# MCU_SEC.net
KiCad netlist of a schematic drawn in Altium Designer
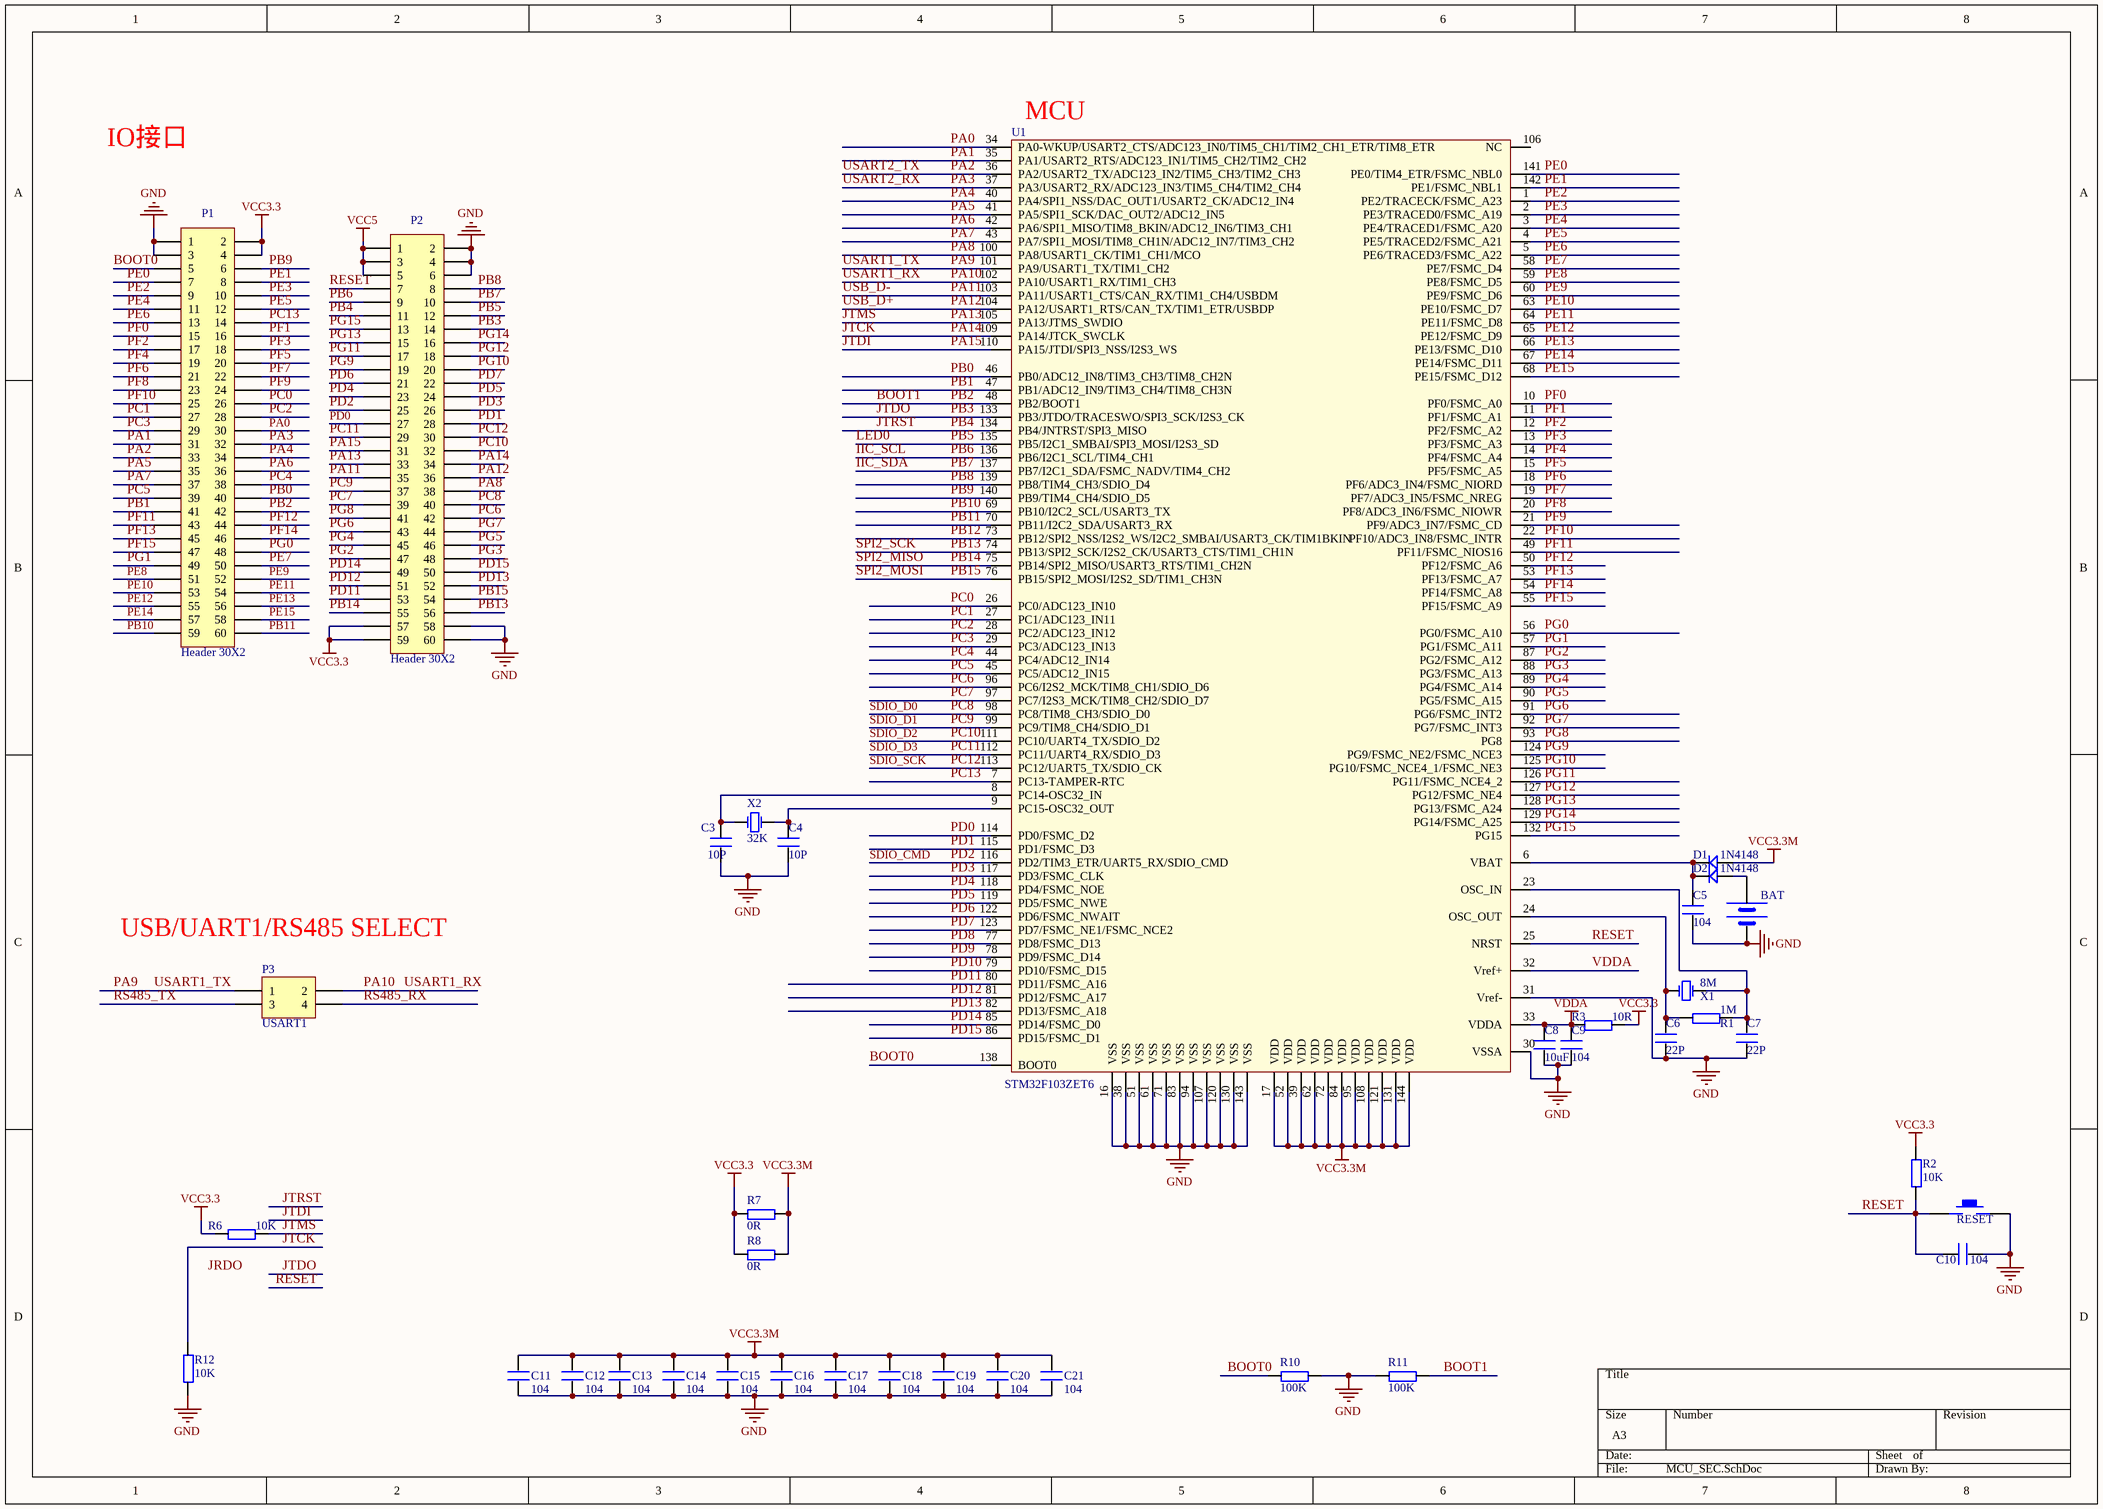
[diagram p0: MCU_SEC.SchDoc]

(export (version "E")
  (design (tool "Eeschema 10.0.6"))
  (components
    (comp (ref "BAT") (value "BATT") (footprint "BATML") (libsource (lib "战舰STM32开发板底板封装库") (part "BAT")))
    (comp (ref "C3") (value "10P") (footprint "0603CL") (libsource (lib "战舰STM32开发板底板封装库") (part "C")))
    (comp (ref "C4") (value "10P") (footprint "0603CL") (libsource (lib "战舰STM32开发板底板封装库") (part "C")))
    (comp (ref "C5") (value "104") (footprint "0603CL") (libsource (lib "战舰STM32开发板底板封装库") (part "C")))
    (comp (ref "C6") (value "22P") (footprint "0603CL") (libsource (lib "战舰STM32开发板底板封装库") (part "C")))
    (comp (ref "C7") (value "22P") (footprint "0603CL") (libsource (lib "战舰STM32开发板底板封装库") (part "C")))
    (comp (ref "C8") (value "10uF") (footprint "0603CL") (libsource (lib "战舰STM32开发板底板封装库") (part "C")))
    (comp (ref "C9") (value "104") (footprint "0603CL") (libsource (lib "战舰STM32开发板底板封装库") (part "C")))
    (comp (ref "C10") (value "104") (footprint "0603CL") (libsource (lib "战舰STM32开发板底板封装库") (part "C")))
    (comp (ref "C11") (value "104") (footprint "0603CL") (libsource (lib "战舰STM32开发板底板封装库") (part "C")))
    (comp (ref "C12") (value "104") (footprint "0603CL") (libsource (lib "战舰STM32开发板底板封装库") (part "C")))
    (comp (ref "C13") (value "104") (footprint "0603CL") (libsource (lib "战舰STM32开发板底板封装库") (part "C")))
    (comp (ref "C14") (value "104") (footprint "0603CL") (libsource (lib "战舰STM32开发板底板封装库") (part "C")))
    (comp (ref "C15") (value "104") (footprint "0603CL") (libsource (lib "战舰STM32开发板底板封装库") (part "C")))
    (comp (ref "C16") (value "104") (footprint "0603CL") (libsource (lib "战舰STM32开发板底板封装库") (part "C")))
    (comp (ref "C17") (value "104") (footprint "0603CL") (libsource (lib "战舰STM32开发板底板封装库") (part "C")))
    (comp (ref "C18") (value "104") (footprint "0603CL") (libsource (lib "战舰STM32开发板底板封装库") (part "C")))
    (comp (ref "C19") (value "104") (footprint "0603CL") (libsource (lib "战舰STM32开发板底板封装库") (part "C")))
    (comp (ref "C20") (value "104") (footprint "0603CL") (libsource (lib "战舰STM32开发板底板封装库") (part "C")))
    (comp (ref "C21") (value "104") (footprint "0603CL") (libsource (lib "战舰STM32开发板底板封装库") (part "C")))
    (comp (ref "D1")
      (value "1N4148")
      (footprint "LL-34(1/2)L")
      (libsource (lib "战舰STM32开发板底板封装库") (part "D"))
    )
    (comp (ref "D2")
      (value "1N4148")
      (footprint "LL-34(1/2)L")
      (libsource (lib "战舰STM32开发板底板封装库") (part "D"))
    )
    (comp (ref "P1")
      (value "Header 30X2")
      (footprint "HDR2X30")
      (description "Header, 30-Pin, Dual row")
      (fields (field (name "PUBLISHER") "Altium Limited"))
      (libsource (lib "Miscellaneous Connectors") (part "Header 30X2"))
    )
    (comp (ref "P2")
      (value "Header 30X2")
      (footprint "HDR2X30")
      (description "Header, 30-Pin, Dual row")
      (fields (field (name "PUBLISHER") "Altium Limited"))
      (libsource (lib "Miscellaneous Connectors") (part "Header 30X2"))
    )
    (comp (ref "P3")
      (value "USART1")
      (footprint "HDR2X2")
      (description "Header, 2-Pin, Dual row")
      (fields (field (name "PUBLISHER") "Altium Limited"))
      (libsource (lib "Miscellaneous Connectors") (part "Header 2X2"))
    )
    (comp (ref "R1") (value "1M") (footprint "0603L") (libsource (lib "战舰STM32开发板底板封装库") (part "R")))
    (comp (ref "R2") (value "10K") (footprint "0603L") (libsource (lib "战舰STM32开发板底板封装库") (part "R")))
    (comp (ref "R3") (value "10R") (footprint "0603L") (libsource (lib "战舰STM32开发板底板封装库") (part "R")))
    (comp (ref "R6") (value "10K") (footprint "0603L") (libsource (lib "战舰STM32开发板底板封装库") (part "R")))
    (comp (ref "R7") (value "0R") (footprint "0603L") (libsource (lib "战舰STM32开发板底板封装库") (part "R")))
    (comp (ref "R8") (value "0R") (footprint "0603L") (libsource (lib "战舰STM32开发板底板封装库") (part "R")))
    (comp (ref "R10") (value "100K") (footprint "0603L") (libsource (lib "战舰STM32开发板底板封装库") (part "R")))
    (comp (ref "R11") (value "100K") (footprint "0603L") (libsource (lib "战舰STM32开发板底板封装库") (part "R")))
    (comp (ref "R12") (value "10K") (footprint "0603L") (libsource (lib "战舰STM32开发板底板封装库") (part "R")))
    (comp (ref "RESET")
      (value "KEY_M")
      (footprint "SW2 - MINI1")
      (libsource (lib "战舰STM32开发板底板封装库") (part "KEY_M"))
    )
    (comp (ref "U1")
      (value "STM32F103ZET6")
      (footprint "LQFP144L")
      (libsource (lib "战舰STM32开发板底板封装库") (part "STM32F103ZET6"))
    )
    (comp (ref "X1")
      (value "8M")
      (footprint "OSC-5032-2P")
      (description "Crystal Oscillator")
      (fields (field (name "PUBLISHER") "Altium Limited"))
      (libsource (lib "常用元件库") (part "XTAL_1"))
    )
    (comp (ref "X2")
      (value "32K")
      (footprint "OSC-306")
      (description "Crystal Oscillator")
      (fields (field (name "PUBLISHER") "Altium Limited"))
      (libsource (lib "常用元件库") (part "XTAL_1"))
    )
  )
  (nets
    (net (code "1") (name "/BOOT0") (class "Default")
      (node (ref "P1") (pin "5") (pinfunction "5_5") (pintype "passive"))
      (node (ref "R10") (pin "1") (pintype "passive"))
      (node (ref "U1") (pin "138") (pinfunction "BOOT0_138") (pintype "passive"))
    )
    (net (code "2") (name "/BOOT1") (class "Default")
      (node (ref "P1") (pin "42") (pinfunction "42_42") (pintype "passive"))
      (node (ref "R11") (pin "2") (pintype "passive"))
      (node (ref "U1") (pin "48") (pinfunction "PB2/BOOT1_48") (pintype "passive"))
    )
    (net (code "3") (name "/IIC_SCL") (class "Default")
      (node (ref "P2") (pin "9") (pinfunction "9_9") (pintype "passive"))
      (node (ref "U1") (pin "136") (pinfunction "PB6/I2C1_SCL/TIM4_CH1_136") (pintype "passive"))
    )
    (net (code "4") (name "/IIC_SDA") (class "Default")
      (node (ref "P2") (pin "10") (pinfunction "10_10") (pintype "passive"))
      (node (ref "U1") (pin "137") (pinfunction "PB7/I2C1_SDA/FSMC_NADV/TIM4_CH2_137") (pintype "passive"))
    )
    (net (code "6") (name "/JTCK") (class "Default")
      (node (ref "P2") (pin "34") (pinfunction "34_34") (pintype "passive"))
      (node (ref "R12") (pin "2") (pintype "passive"))
      (node (ref "U1") (pin "109") (pinfunction "PA14/JTCK_SWCLK_109") (pintype "passive"))
    )
    (net (code "7") (name "/JTDI") (class "Default")
      (node (ref "P2") (pin "31") (pinfunction "31_31") (pintype "passive"))
      (node (ref "U1") (pin "110") (pinfunction "PA15/JTDI/SPI3_NSS/I2S3_WS_110") (pintype "passive"))
    )
    (net (code "8") (name "/JTDO") (class "Default")
      (node (ref "P2") (pin "14") (pinfunction "14_14") (pintype "passive"))
      (node (ref "U1") (pin "133") (pinfunction "PB3/JTDO/TRACESWO/SPI3_SCK/I2S3_CK_133") (pintype "passive"))
    )
    (net (code "9") (name "/JTMS") (class "Default")
      (node (ref "P2") (pin "33") (pinfunction "33_33") (pintype "passive"))
      (node (ref "R6") (pin "2") (pintype "passive"))
      (node (ref "U1") (pin "105") (pinfunction "PA13/JTMS_SWDIO_105") (pintype "passive"))
    )
    (net (code "10") (name "/JTRST") (class "Default")
      (node (ref "P2") (pin "11") (pinfunction "11_11") (pintype "passive"))
      (node (ref "U1") (pin "134") (pinfunction "PB4/JNTRST/SPI3_MISO_134") (pintype "passive"))
    )
    (net (code "11") (name "/LED0") (class "Default")
      (node (ref "P2") (pin "12") (pinfunction "12_12") (pintype "passive"))
      (node (ref "U1") (pin "135") (pinfunction "PB5/I2C1_SMBAI/SPI3_MOSI/I2S3_SD_135") (pintype "passive"))
    )
    (net (code "12") (name "/PA0") (class "Default")
      (node (ref "P1") (pin "30") (pinfunction "30_30") (pintype "passive"))
      (node (ref "U1") (pin "34") (pinfunction "PA0-WKUP/USART2_CTS/ADC123_IN0/TIM5_CH1/TIM2_CH1_ETR/TIM8_ETR_34") (pintype "passive"))
    )
    (net (code "13") (name "/PA1") (class "Default")
      (node (ref "P1") (pin "31") (pinfunction "31_31") (pintype "passive"))
      (node (ref "U1") (pin "35") (pinfunction "PA1/USART2_RTS/ADC123_IN1/TIM5_CH2/TIM2_CH2_35") (pintype "passive"))
    )
    (net (code "14") (name "/PA2") (class "Default")
      (node (ref "P1") (pin "33") (pinfunction "33_33") (pintype "passive"))
      (node (ref "U1") (pin "36") (pinfunction "PA2/USART2_TX/ADC123_IN2/TIM5_CH3/TIM2_CH3_36") (pintype "passive"))
    )
    (net (code "15") (name "/PA3") (class "Default")
      (node (ref "P1") (pin "32") (pinfunction "32_32") (pintype "passive"))
      (node (ref "U1") (pin "37") (pinfunction "PA3/USART2_RX/ADC123_IN3/TIM5_CH4/TIM2_CH4_37") (pintype "passive"))
    )
    (net (code "16") (name "/PA4") (class "Default")
      (node (ref "P1") (pin "34") (pinfunction "34_34") (pintype "passive"))
      (node (ref "U1") (pin "40") (pinfunction "PA4/SPI1_NSS/DAC_OUT1/USART2_CK/ADC12_IN4_40") (pintype "passive"))
    )
    (net (code "17") (name "/PA5") (class "Default")
      (node (ref "P1") (pin "35") (pinfunction "35_35") (pintype "passive"))
      (node (ref "U1") (pin "41") (pinfunction "PA5/SPI1_SCK/DAC_OUT2/ADC12_IN5_41") (pintype "passive"))
    )
    (net (code "18") (name "/PA6") (class "Default")
      (node (ref "P1") (pin "36") (pinfunction "36_36") (pintype "passive"))
      (node (ref "U1") (pin "42") (pinfunction "PA6/SPI1_MISO/TIM8_BKIN/ADC12_IN6/TIM3_CH1_42") (pintype "passive"))
    )
    (net (code "19") (name "/PA7") (class "Default")
      (node (ref "P1") (pin "37") (pinfunction "37_37") (pintype "passive"))
      (node (ref "U1") (pin "43") (pinfunction "PA7/SPI1_MOSI/TIM8_CH1N/ADC12_IN7/TIM3_CH2_43") (pintype "passive"))
    )
    (net (code "20") (name "/PA8") (class "Default")
      (node (ref "P2") (pin "38") (pinfunction "38_38") (pintype "passive"))
      (node (ref "U1") (pin "100") (pinfunction "PA8/USART1_CK/TIM1_CH1/MCO_100") (pintype "passive"))
    )
    (net (code "21") (name "/PA9") (class "Default")
      (node (ref "P3") (pin "1") (pinfunction "1_1") (pintype "passive"))
      (node (ref "U1") (pin "101") (pinfunction "PA9/USART1_TX/TIM1_CH2_101") (pintype "passive"))
    )
    (net (code "22") (name "/PA10") (class "Default")
      (node (ref "P3") (pin "2") (pinfunction "2_2") (pintype "passive"))
      (node (ref "U1") (pin "102") (pinfunction "PA10/USART1_RX/TIM1_CH3_102") (pintype "passive"))
    )
    (net (code "23") (name "/PA11") (class "Default")
      (node (ref "P2") (pin "35") (pinfunction "35_35") (pintype "passive"))
      (node (ref "U1") (pin "103") (pinfunction "PA11/USART1_CTS/CAN_RX/TIM1_CH4/USBDM_103") (pintype "passive"))
    )
    (net (code "24") (name "/PA12") (class "Default")
      (node (ref "P2") (pin "36") (pinfunction "36_36") (pintype "passive"))
      (node (ref "U1") (pin "104") (pinfunction "PA12/USART1_RTS/CAN_TX/TIM1_ETR/USBDP_104") (pintype "passive"))
    )
    (net (code "25") (name "/PB0") (class "Default")
      (node (ref "P1") (pin "40") (pinfunction "40_40") (pintype "passive"))
      (node (ref "U1") (pin "46") (pinfunction "PB0/ADC12_IN8/TIM3_CH3/TIM8_CH2N_46") (pintype "passive"))
    )
    (net (code "26") (name "/PB1") (class "Default")
      (node (ref "P1") (pin "41") (pinfunction "41_41") (pintype "passive"))
      (node (ref "U1") (pin "47") (pinfunction "PB1/ADC12_IN9/TIM3_CH4/TIM8_CH3N_47") (pintype "passive"))
    )
    (net (code "27") (name "/PB8") (class "Default")
      (node (ref "P2") (pin "8") (pinfunction "8_8") (pintype "passive"))
      (node (ref "U1") (pin "139") (pinfunction "PB8/TIM4_CH3/SDIO_D4_139") (pintype "passive"))
    )
    (net (code "28") (name "/PB9") (class "Default")
      (node (ref "P1") (pin "6") (pinfunction "6_6") (pintype "passive"))
      (node (ref "U1") (pin "140") (pinfunction "PB9/TIM4_CH4/SDIO_D5_140") (pintype "passive"))
    )
    (net (code "29") (name "/PB10") (class "Default")
      (node (ref "P1") (pin "59") (pinfunction "59_59") (pintype "passive"))
      (node (ref "U1") (pin "69") (pinfunction "PB10/I2C2_SCL/USART3_TX_69") (pintype "passive"))
    )
    (net (code "30") (name "/PB11") (class "Default")
      (node (ref "P1") (pin "60") (pinfunction "60_60") (pintype "passive"))
      (node (ref "U1") (pin "70") (pinfunction "PB11/I2C2_SDA/USART3_RX_70") (pintype "passive"))
    )
    (net (code "31") (name "/PB12") (class "Default")
      (node (ref "U1") (pin "73") (pinfunction "PB12/SPI2_NSS/I2S2_WS/I2C2_SMBAI/USART3_CK/TIM1BKIN_73") (pintype "passive"))
    )
    (net (code "32") (name "/PB13") (class "Default")
      (node (ref "P2") (pin "56") (pinfunction "56_56") (pintype "passive"))
      (node (ref "U1") (pin "74") (pinfunction "PB13/SPI2_SCK/I2S2_CK/USART3_CTS/TIM1_CH1N_74") (pintype "passive"))
    )
    (net (code "33") (name "/PB14") (class "Default")
      (node (ref "P2") (pin "55") (pinfunction "55_55") (pintype "passive"))
      (node (ref "U1") (pin "75") (pinfunction "PB14/SPI2_MISO/USART3_RTS/TIM1_CH2N_75") (pintype "passive"))
    )
    (net (code "34") (name "/PB15") (class "Default")
      (node (ref "P2") (pin "54") (pinfunction "54_54") (pintype "passive"))
      (node (ref "U1") (pin "76") (pinfunction "PB15/SPI2_MOSI/I2S2_SD/TIM1_CH3N_76") (pintype "passive"))
    )
    (net (code "35") (name "/PC0") (class "Default")
      (node (ref "P1") (pin "26") (pinfunction "26_26") (pintype "passive"))
      (node (ref "U1") (pin "26") (pinfunction "PC0/ADC123_IN10_26") (pintype "passive"))
    )
    (net (code "36") (name "/PC1") (class "Default")
      (node (ref "P1") (pin "27") (pinfunction "27_27") (pintype "passive"))
      (node (ref "U1") (pin "27") (pinfunction "PC1/ADC123_IN11_27") (pintype "passive"))
    )
    (net (code "37") (name "/PC2") (class "Default")
      (node (ref "P1") (pin "28") (pinfunction "28_28") (pintype "passive"))
      (node (ref "U1") (pin "28") (pinfunction "PC2/ADC123_IN12_28") (pintype "passive"))
    )
    (net (code "38") (name "/PC3") (class "Default")
      (node (ref "P1") (pin "29") (pinfunction "29_29") (pintype "passive"))
      (node (ref "U1") (pin "29") (pinfunction "PC3/ADC123_IN13_29") (pintype "passive"))
    )
    (net (code "39") (name "/PC4") (class "Default")
      (node (ref "P1") (pin "38") (pinfunction "38_38") (pintype "passive"))
      (node (ref "U1") (pin "44") (pinfunction "PC4/ADC12_IN14_44") (pintype "passive"))
    )
    (net (code "40") (name "/PC5") (class "Default")
      (node (ref "P1") (pin "39") (pinfunction "39_39") (pintype "passive"))
      (node (ref "U1") (pin "45") (pinfunction "PC5/ADC12_IN15_45") (pintype "passive"))
    )
    (net (code "41") (name "/PC6") (class "Default")
      (node (ref "P2") (pin "42") (pinfunction "42_42") (pintype "passive"))
      (node (ref "U1") (pin "96") (pinfunction "PC6/I2S2_MCK/TIM8_CH1/SDIO_D6_96") (pintype "passive"))
    )
    (net (code "42") (name "/PC7") (class "Default")
      (node (ref "P2") (pin "39") (pinfunction "39_39") (pintype "passive"))
      (node (ref "U1") (pin "97") (pinfunction "PC7/I2S3_MCK/TIM8_CH2/SDIO_D7_97") (pintype "passive"))
    )
    (net (code "43") (name "/PC8") (class "Default")
      (node (ref "P2") (pin "40") (pinfunction "40_40") (pintype "passive"))
      (node (ref "U1") (pin "98") (pinfunction "PC8/TIM8_CH3/SDIO_D0_98") (pintype "passive"))
    )
    (net (code "44") (name "/PC9") (class "Default")
      (node (ref "P2") (pin "37") (pinfunction "37_37") (pintype "passive"))
      (node (ref "U1") (pin "99") (pinfunction "PC9/TIM8_CH4/SDIO_D1_99") (pintype "passive"))
    )
    (net (code "45") (name "/PC10") (class "Default")
      (node (ref "P2") (pin "32") (pinfunction "32_32") (pintype "passive"))
      (node (ref "U1") (pin "111") (pinfunction "PC10/UART4_TX/SDIO_D2_111") (pintype "passive"))
    )
    (net (code "46") (name "/PC11") (class "Default")
      (node (ref "P2") (pin "29") (pinfunction "29_29") (pintype "passive"))
      (node (ref "U1") (pin "112") (pinfunction "PC11/UART4_RX/SDIO_D3_112") (pintype "passive"))
    )
    (net (code "47") (name "/PC12") (class "Default")
      (node (ref "P2") (pin "30") (pinfunction "30_30") (pintype "passive"))
      (node (ref "U1") (pin "113") (pinfunction "PC12/UART5_TX/SDIO_CK_113") (pintype "passive"))
    )
    (net (code "48") (name "/PC13") (class "Default")
      (node (ref "P1") (pin "14") (pinfunction "14_14") (pintype "passive"))
      (node (ref "U1") (pin "7") (pinfunction "PC13-TAMPER-RTC_7") (pintype "passive"))
    )
    (net (code "49") (name "/PD0") (class "Default")
      (node (ref "P2") (pin "27") (pinfunction "27_27") (pintype "passive"))
      (node (ref "U1") (pin "114") (pinfunction "PD0/FSMC_D2_114") (pintype "passive"))
    )
    (net (code "50") (name "/PD1") (class "Default")
      (node (ref "P2") (pin "28") (pinfunction "28_28") (pintype "passive"))
      (node (ref "U1") (pin "115") (pinfunction "PD1/FSMC_D3_115") (pintype "passive"))
    )
    (net (code "51") (name "/PD2") (class "Default")
      (node (ref "P2") (pin "25") (pinfunction "25_25") (pintype "passive"))
      (node (ref "U1") (pin "116") (pinfunction "PD2/TIM3_ETR/UART5_RX/SDIO_CMD_116") (pintype "passive"))
    )
    (net (code "52") (name "/PD3") (class "Default")
      (node (ref "P2") (pin "26") (pinfunction "26_26") (pintype "passive"))
      (node (ref "U1") (pin "117") (pinfunction "PD3/FSMC_CLK_117") (pintype "passive"))
    )
    (net (code "53") (name "/PD4") (class "Default")
      (node (ref "P2") (pin "23") (pinfunction "23_23") (pintype "passive"))
      (node (ref "U1") (pin "118") (pinfunction "PD4/FSMC_NOE_118") (pintype "passive"))
    )
    (net (code "54") (name "/PD5") (class "Default")
      (node (ref "P2") (pin "24") (pinfunction "24_24") (pintype "passive"))
      (node (ref "U1") (pin "119") (pinfunction "PD5/FSMC_NWE_119") (pintype "passive"))
    )
    (net (code "55") (name "/PD6") (class "Default")
      (node (ref "P2") (pin "21") (pinfunction "21_21") (pintype "passive"))
      (node (ref "U1") (pin "122") (pinfunction "PD6/FSMC_NWAIT_122") (pintype "passive"))
    )
    (net (code "56") (name "/PD7") (class "Default")
      (node (ref "P2") (pin "22") (pinfunction "22_22") (pintype "passive"))
      (node (ref "U1") (pin "123") (pinfunction "PD7/FSMC_NE1/FSMC_NCE2_123") (pintype "passive"))
    )
    (net (code "57") (name "/PD8") (class "Default")
      (node (ref "U1") (pin "77") (pinfunction "PD8/FSMC_D13_77") (pintype "passive"))
    )
    (net (code "58") (name "/PD9") (class "Default")
      (node (ref "U1") (pin "78") (pinfunction "PD9/FSMC_D14_78") (pintype "passive"))
    )
    (net (code "59") (name "/PD10") (class "Default")
      (node (ref "U1") (pin "79") (pinfunction "PD10/FSMC_D15_79") (pintype "passive"))
    )
    (net (code "60") (name "/PD11") (class "Default")
      (node (ref "P2") (pin "53") (pinfunction "53_53") (pintype "passive"))
      (node (ref "U1") (pin "80") (pinfunction "PD11/FSMC_A16_80") (pintype "passive"))
    )
    (net (code "61") (name "/PD12") (class "Default")
      (node (ref "P2") (pin "51") (pinfunction "51_51") (pintype "passive"))
      (node (ref "U1") (pin "81") (pinfunction "PD12/FSMC_A17_81") (pintype "passive"))
    )
    (net (code "62") (name "/PD13") (class "Default")
      (node (ref "P2") (pin "52") (pinfunction "52_52") (pintype "passive"))
      (node (ref "U1") (pin "82") (pinfunction "PD13/FSMC_A18_82") (pintype "passive"))
    )
    (net (code "63") (name "/PD14") (class "Default")
      (node (ref "P2") (pin "49") (pinfunction "49_49") (pintype "passive"))
      (node (ref "U1") (pin "85") (pinfunction "PD14/FSMC_D0_85") (pintype "passive"))
    )
    (net (code "64") (name "/PD15") (class "Default")
      (node (ref "P2") (pin "50") (pinfunction "50_50") (pintype "passive"))
      (node (ref "U1") (pin "86") (pinfunction "PD15/FSMC_D1_86") (pintype "passive"))
    )
    (net (code "65") (name "/PE0") (class "Default")
      (node (ref "P1") (pin "7") (pinfunction "7_7") (pintype "passive"))
      (node (ref "U1") (pin "141") (pinfunction "PE0/TIM4_ETR/FSMC_NBL0_141") (pintype "passive"))
    )
    (net (code "66") (name "/PE1") (class "Default")
      (node (ref "P1") (pin "8") (pinfunction "8_8") (pintype "passive"))
      (node (ref "U1") (pin "142") (pinfunction "PE1/FSMC_NBL1_142") (pintype "passive"))
    )
    (net (code "67") (name "/PE2") (class "Default")
      (node (ref "P1") (pin "9") (pinfunction "9_9") (pintype "passive"))
      (node (ref "U1") (pin "1") (pinfunction "PE2/TRACECK/FSMC_A23_1") (pintype "passive"))
    )
    (net (code "68") (name "/PE3") (class "Default")
      (node (ref "P1") (pin "10") (pinfunction "10_10") (pintype "passive"))
      (node (ref "U1") (pin "2") (pinfunction "PE3/TRACED0/FSMC_A19_2") (pintype "passive"))
    )
    (net (code "69") (name "/PE4") (class "Default")
      (node (ref "P1") (pin "11") (pinfunction "11_11") (pintype "passive"))
      (node (ref "U1") (pin "3") (pinfunction "PE4/TRACED1/FSMC_A20_3") (pintype "passive"))
    )
    (net (code "70") (name "/PE5") (class "Default")
      (node (ref "P1") (pin "12") (pinfunction "12_12") (pintype "passive"))
      (node (ref "U1") (pin "4") (pinfunction "PE5/TRACED2/FSMC_A21_4") (pintype "passive"))
    )
    (net (code "71") (name "/PE6") (class "Default")
      (node (ref "P1") (pin "13") (pinfunction "13_13") (pintype "passive"))
      (node (ref "U1") (pin "5") (pinfunction "PE6/TRACED3/FSMC_A22_5") (pintype "passive"))
    )
    (net (code "72") (name "/PE7") (class "Default")
      (node (ref "P1") (pin "50") (pinfunction "50_50") (pintype "passive"))
      (node (ref "U1") (pin "58") (pinfunction "PE7/FSMC_D4_58") (pintype "passive"))
    )
    (net (code "73") (name "/PE8") (class "Default")
      (node (ref "P1") (pin "51") (pinfunction "51_51") (pintype "passive"))
      (node (ref "U1") (pin "59") (pinfunction "PE8/FSMC_D5_59") (pintype "passive"))
    )
    (net (code "74") (name "/PE9") (class "Default")
      (node (ref "P1") (pin "52") (pinfunction "52_52") (pintype "passive"))
      (node (ref "U1") (pin "60") (pinfunction "PE9/FSMC_D6_60") (pintype "passive"))
    )
    (net (code "75") (name "/PE10") (class "Default")
      (node (ref "P1") (pin "53") (pinfunction "53_53") (pintype "passive"))
      (node (ref "U1") (pin "63") (pinfunction "PE10/FSMC_D7_63") (pintype "passive"))
    )
    (net (code "76") (name "/PE11") (class "Default")
      (node (ref "P1") (pin "54") (pinfunction "54_54") (pintype "passive"))
      (node (ref "U1") (pin "64") (pinfunction "PE11/FSMC_D8_64") (pintype "passive"))
    )
    (net (code "77") (name "/PE12") (class "Default")
      (node (ref "P1") (pin "55") (pinfunction "55_55") (pintype "passive"))
      (node (ref "U1") (pin "65") (pinfunction "PE12/FSMC_D9_65") (pintype "passive"))
    )
    (net (code "78") (name "/PE13") (class "Default")
      (node (ref "P1") (pin "56") (pinfunction "56_56") (pintype "passive"))
      (node (ref "U1") (pin "66") (pinfunction "PE13/FSMC_D10_66") (pintype "passive"))
    )
    (net (code "79") (name "/PE14") (class "Default")
      (node (ref "P1") (pin "57") (pinfunction "57_57") (pintype "passive"))
      (node (ref "U1") (pin "67") (pinfunction "PE14/FSMC_D11_67") (pintype "passive"))
    )
    (net (code "80") (name "/PE15") (class "Default")
      (node (ref "P1") (pin "58") (pinfunction "58_58") (pintype "passive"))
      (node (ref "U1") (pin "68") (pinfunction "PE15/FSMC_D12_68") (pintype "passive"))
    )
    (net (code "81") (name "/PF0") (class "Default")
      (node (ref "P1") (pin "15") (pinfunction "15_15") (pintype "passive"))
      (node (ref "U1") (pin "10") (pinfunction "PF0/FSMC_A0_10") (pintype "passive"))
    )
    (net (code "82") (name "/PF1") (class "Default")
      (node (ref "P1") (pin "16") (pinfunction "16_16") (pintype "passive"))
      (node (ref "U1") (pin "11") (pinfunction "PF1/FSMC_A1_11") (pintype "passive"))
    )
    (net (code "83") (name "/PF2") (class "Default")
      (node (ref "P1") (pin "17") (pinfunction "17_17") (pintype "passive"))
      (node (ref "U1") (pin "12") (pinfunction "PF2/FSMC_A2_12") (pintype "passive"))
    )
    (net (code "84") (name "/PF3") (class "Default")
      (node (ref "P1") (pin "18") (pinfunction "18_18") (pintype "passive"))
      (node (ref "U1") (pin "13") (pinfunction "PF3/FSMC_A3_13") (pintype "passive"))
    )
    (net (code "85") (name "/PF4") (class "Default")
      (node (ref "P1") (pin "19") (pinfunction "19_19") (pintype "passive"))
      (node (ref "U1") (pin "14") (pinfunction "PF4/FSMC_A4_14") (pintype "passive"))
    )
    (net (code "86") (name "/PF5") (class "Default")
      (node (ref "P1") (pin "20") (pinfunction "20_20") (pintype "passive"))
      (node (ref "U1") (pin "15") (pinfunction "PF5/FSMC_A5_15") (pintype "passive"))
    )
    (net (code "87") (name "/PF6") (class "Default")
      (node (ref "P1") (pin "21") (pinfunction "21_21") (pintype "passive"))
      (node (ref "U1") (pin "18") (pinfunction "PF6/ADC3_IN4/FSMC_NIORD_18") (pintype "passive"))
    )
    (net (code "88") (name "/PF7") (class "Default")
      (node (ref "P1") (pin "22") (pinfunction "22_22") (pintype "passive"))
      (node (ref "U1") (pin "19") (pinfunction "PF7/ADC3_IN5/FSMC_NREG_19") (pintype "passive"))
    )
    (net (code "89") (name "/PF8") (class "Default")
      (node (ref "P1") (pin "23") (pinfunction "23_23") (pintype "passive"))
      (node (ref "U1") (pin "20") (pinfunction "PF8/ADC3_IN6/FSMC_NIOWR_20") (pintype "passive"))
    )
    (net (code "90") (name "/PF9") (class "Default")
      (node (ref "P1") (pin "24") (pinfunction "24_24") (pintype "passive"))
      (node (ref "U1") (pin "21") (pinfunction "PF9/ADC3_IN7/FSMC_CD_21") (pintype "passive"))
    )
    (net (code "91") (name "/PF10") (class "Default")
      (node (ref "P1") (pin "25") (pinfunction "25_25") (pintype "passive"))
      (node (ref "U1") (pin "22") (pinfunction "PF10/ADC3_IN8/FSMC_INTR_22") (pintype "passive"))
    )
    (net (code "92") (name "/PF11") (class "Default")
      (node (ref "P1") (pin "43") (pinfunction "43_43") (pintype "passive"))
      (node (ref "U1") (pin "49") (pinfunction "PF11/FSMC_NIOS16_49") (pintype "passive"))
    )
    (net (code "93") (name "/PF12") (class "Default")
      (node (ref "P1") (pin "44") (pinfunction "44_44") (pintype "passive"))
      (node (ref "U1") (pin "50") (pinfunction "PF12/FSMC_A6_50") (pintype "passive"))
    )
    (net (code "94") (name "/PF13") (class "Default")
      (node (ref "P1") (pin "45") (pinfunction "45_45") (pintype "passive"))
      (node (ref "U1") (pin "53") (pinfunction "PF13/FSMC_A7_53") (pintype "passive"))
    )
    (net (code "95") (name "/PF14") (class "Default")
      (node (ref "P1") (pin "46") (pinfunction "46_46") (pintype "passive"))
      (node (ref "U1") (pin "54") (pinfunction "PF14/FSMC_A8_54") (pintype "passive"))
    )
    (net (code "96") (name "/PF15") (class "Default")
      (node (ref "P1") (pin "47") (pinfunction "47_47") (pintype "passive"))
      (node (ref "U1") (pin "55") (pinfunction "PF15/FSMC_A9_55") (pintype "passive"))
    )
    (net (code "97") (name "/PG0") (class "Default")
      (node (ref "P1") (pin "48") (pinfunction "48_48") (pintype "passive"))
      (node (ref "U1") (pin "56") (pinfunction "PG0/FSMC_A10_56") (pintype "passive"))
    )
    (net (code "98") (name "/PG1") (class "Default")
      (node (ref "P1") (pin "49") (pinfunction "49_49") (pintype "passive"))
      (node (ref "U1") (pin "57") (pinfunction "PG1/FSMC_A11_57") (pintype "passive"))
    )
    (net (code "99") (name "/PG2") (class "Default")
      (node (ref "P2") (pin "47") (pinfunction "47_47") (pintype "passive"))
      (node (ref "U1") (pin "87") (pinfunction "PG2/FSMC_A12_87") (pintype "passive"))
    )
    (net (code "100") (name "/PG3") (class "Default")
      (node (ref "P2") (pin "48") (pinfunction "48_48") (pintype "passive"))
      (node (ref "U1") (pin "88") (pinfunction "PG3/FSMC_A13_88") (pintype "passive"))
    )
    (net (code "101") (name "/PG4") (class "Default")
      (node (ref "P2") (pin "45") (pinfunction "45_45") (pintype "passive"))
      (node (ref "U1") (pin "89") (pinfunction "PG4/FSMC_A14_89") (pintype "passive"))
    )
    (net (code "102") (name "/PG5") (class "Default")
      (node (ref "P2") (pin "46") (pinfunction "46_46") (pintype "passive"))
      (node (ref "U1") (pin "90") (pinfunction "PG5/FSMC_A15_90") (pintype "passive"))
    )
    (net (code "103") (name "/PG6") (class "Default")
      (node (ref "P2") (pin "43") (pinfunction "43_43") (pintype "passive"))
      (node (ref "U1") (pin "91") (pinfunction "PG6/FSMC_INT2_91") (pintype "passive"))
    )
    (net (code "104") (name "/PG7") (class "Default")
      (node (ref "P2") (pin "44") (pinfunction "44_44") (pintype "passive"))
      (node (ref "U1") (pin "92") (pinfunction "PG7/FSMC_INT3_92") (pintype "passive"))
    )
    (net (code "105") (name "/PG8") (class "Default")
      (node (ref "P2") (pin "41") (pinfunction "41_41") (pintype "passive"))
      (node (ref "U1") (pin "93") (pinfunction "PG8_93") (pintype "passive"))
    )
    (net (code "106") (name "/PG9") (class "Default")
      (node (ref "P2") (pin "19") (pinfunction "19_19") (pintype "passive"))
      (node (ref "U1") (pin "124") (pinfunction "PG9/FSMC_NE2/FSMC_NCE3_124") (pintype "passive"))
    )
    (net (code "107") (name "/PG10") (class "Default")
      (node (ref "P2") (pin "20") (pinfunction "20_20") (pintype "passive"))
      (node (ref "U1") (pin "125") (pinfunction "PG10/FSMC_NCE4_1/FSMC_NE3_125") (pintype "passive"))
    )
    (net (code "108") (name "/PG11") (class "Default")
      (node (ref "P2") (pin "17") (pinfunction "17_17") (pintype "passive"))
      (node (ref "U1") (pin "126") (pinfunction "PG11/FSMC_NCE4_2_126") (pintype "passive"))
    )
    (net (code "109") (name "/PG12") (class "Default")
      (node (ref "P2") (pin "18") (pinfunction "18_18") (pintype "passive"))
      (node (ref "U1") (pin "127") (pinfunction "PG12/FSMC_NE4_127") (pintype "passive"))
    )
    (net (code "110") (name "/PG13") (class "Default")
      (node (ref "P2") (pin "15") (pinfunction "15_15") (pintype "passive"))
      (node (ref "U1") (pin "128") (pinfunction "PG13/FSMC_A24_128") (pintype "passive"))
    )
    (net (code "111") (name "/PG14") (class "Default")
      (node (ref "P2") (pin "16") (pinfunction "16_16") (pintype "passive"))
      (node (ref "U1") (pin "129") (pinfunction "PG14/FSMC_A25_129") (pintype "passive"))
    )
    (net (code "112") (name "/PG15") (class "Default")
      (node (ref "P2") (pin "13") (pinfunction "13_13") (pintype "passive"))
      (node (ref "U1") (pin "132") (pinfunction "PG15_132") (pintype "passive"))
    )
    (net (code "113") (name "/RESET") (class "Default")
      (node (ref "C10") (pin "2") (pintype "passive"))
      (node (ref "P2") (pin "7") (pinfunction "7_7") (pintype "passive"))
      (node (ref "R2") (pin "1") (pintype "passive"))
      (node (ref "RESET") (pin "1") (pinfunction "1_1") (pintype "passive"))
      (node (ref "U1") (pin "25") (pinfunction "NRST_25") (pintype "passive"))
    )
    (net (code "114") (name "/RS485_RX") (class "Default")
      (node (ref "P3") (pin "4") (pinfunction "4_4") (pintype "passive"))
    )
    (net (code "115") (name "/RS485_TX") (class "Default")
      (node (ref "P3") (pin "3") (pinfunction "3_3") (pintype "passive"))
    )
    (net (code "116") (name "GND") (class "Default")
      (node (ref "BAT") (pin "2") (pinfunction "GND_2") (pintype "passive"))
      (node (ref "C10") (pin "1") (pintype "passive"))
      (node (ref "C11") (pin "2") (pintype "passive"))
      (node (ref "C12") (pin "2") (pintype "passive"))
      (node (ref "C13") (pin "2") (pintype "passive"))
      (node (ref "C14") (pin "2") (pintype "passive"))
      (node (ref "C15") (pin "2") (pintype "passive"))
      (node (ref "C16") (pin "2") (pintype "passive"))
      (node (ref "C17") (pin "2") (pintype "passive"))
      (node (ref "C18") (pin "2") (pintype "passive"))
      (node (ref "C19") (pin "2") (pintype "passive"))
      (node (ref "C20") (pin "2") (pintype "passive"))
      (node (ref "C21") (pin "2") (pintype "passive"))
      (node (ref "C3") (pin "1") (pintype "passive"))
      (node (ref "C4") (pin "1") (pintype "passive"))
      (node (ref "C5") (pin "1") (pintype "passive"))
      (node (ref "C6") (pin "1") (pintype "passive"))
      (node (ref "C7") (pin "1") (pintype "passive"))
      (node (ref "C8") (pin "1") (pintype "passive"))
      (node (ref "C9") (pin "1") (pintype "passive"))
      (node (ref "P1") (pin "1") (pinfunction "1_1") (pintype "passive"))
      (node (ref "P1") (pin "3") (pinfunction "3_3") (pintype "passive"))
      (node (ref "P2") (pin "2") (pinfunction "2_2") (pintype "passive"))
      (node (ref "P2") (pin "4") (pinfunction "4_4") (pintype "passive"))
      (node (ref "P2") (pin "58") (pinfunction "58_58") (pintype "passive"))
      (node (ref "P2") (pin "6") (pinfunction "6_6") (pintype "passive"))
      (node (ref "P2") (pin "60") (pinfunction "60_60") (pintype "passive"))
      (node (ref "R10") (pin "2") (pintype "passive"))
      (node (ref "R11") (pin "1") (pintype "passive"))
      (node (ref "R12") (pin "1") (pintype "passive"))
      (node (ref "RESET") (pin "2") (pinfunction "2_2") (pintype "passive"))
      (node (ref "U1") (pin "107") (pinfunction "VSS_107") (pintype "passive"))
      (node (ref "U1") (pin "120") (pinfunction "VSS_120") (pintype "passive"))
      (node (ref "U1") (pin "130") (pinfunction "VSS_130") (pintype "passive"))
      (node (ref "U1") (pin "143") (pinfunction "VSS_143") (pintype "passive"))
      (node (ref "U1") (pin "16") (pinfunction "VSS_16") (pintype "passive"))
      (node (ref "U1") (pin "30") (pinfunction "VSSA_30") (pintype "passive"))
      (node (ref "U1") (pin "31") (pinfunction "Vref-_31") (pintype "passive"))
      (node (ref "U1") (pin "38") (pinfunction "VSS_38") (pintype "passive"))
      (node (ref "U1") (pin "51") (pinfunction "VSS_51") (pintype "passive"))
      (node (ref "U1") (pin "61") (pinfunction "VSS_61") (pintype "passive"))
      (node (ref "U1") (pin "71") (pinfunction "VSS_71") (pintype "passive"))
      (node (ref "U1") (pin "83") (pinfunction "VSS_83") (pintype "passive"))
      (node (ref "U1") (pin "94") (pinfunction "VSS_94") (pintype "passive"))
    )
    (net (code "117") (name "Net-(BAT-VCC)") (class "Default")
      (node (ref "BAT") (pin "1") (pinfunction "VCC_1") (pintype "passive"))
      (node (ref "D2") (pin "1") (pintype "passive"))
    )
    (net (code "118") (name "Net-(U1-OSC_IN)") (class "Default")
      (node (ref "C7") (pin "2") (pintype "passive"))
      (node (ref "R1") (pin "2") (pintype "passive"))
      (node (ref "U1") (pin "23") (pinfunction "OSC_IN_23") (pintype "passive"))
      (node (ref "X1") (pin "2") (pinfunction "OSC2_2") (pintype "passive"))
    )
    (net (code "119") (name "Net-(U1-OSC_OUT)") (class "Default")
      (node (ref "C6") (pin "2") (pintype "passive"))
      (node (ref "R1") (pin "1") (pintype "passive"))
      (node (ref "U1") (pin "24") (pinfunction "OSC_OUT_24") (pintype "passive"))
      (node (ref "X1") (pin "1") (pinfunction "OSC1_1") (pintype "passive"))
    )
    (net (code "120") (name "Net-(U1-PC14-OSC32_IN)") (class "Default")
      (node (ref "C3") (pin "2") (pintype "passive"))
      (node (ref "U1") (pin "8") (pinfunction "PC14-OSC32_IN_8") (pintype "passive"))
      (node (ref "X2") (pin "1") (pinfunction "OSC1_1") (pintype "passive"))
    )
    (net (code "121") (name "Net-(U1-PC15-OSC32_OUT)") (class "Default")
      (node (ref "C4") (pin "2") (pintype "passive"))
      (node (ref "U1") (pin "9") (pinfunction "PC15-OSC32_OUT_9") (pintype "passive"))
      (node (ref "X2") (pin "2") (pinfunction "OSC2_2") (pintype "passive"))
    )
    (net (code "122") (name "Net-(U1-VBAT)") (class "Default")
      (node (ref "C5") (pin "2") (pintype "passive"))
      (node (ref "D1") (pin "2") (pintype "passive"))
      (node (ref "D2") (pin "2") (pintype "passive"))
      (node (ref "U1") (pin "6") (pinfunction "VBAT_6") (pintype "passive"))
    )
    (net (code "123") (name "VCC3.3") (class "Default")
      (node (ref "P1") (pin "2") (pinfunction "2_2") (pintype "passive"))
      (node (ref "P1") (pin "4") (pinfunction "4_4") (pintype "passive"))
      (node (ref "P2") (pin "57") (pinfunction "57_57") (pintype "passive"))
      (node (ref "P2") (pin "59") (pinfunction "59_59") (pintype "passive"))
      (node (ref "R2") (pin "2") (pintype "passive"))
      (node (ref "R3") (pin "2") (pintype "passive"))
      (node (ref "R6") (pin "1") (pintype "passive"))
      (node (ref "R7") (pin "1") (pintype "passive"))
      (node (ref "R8") (pin "1") (pintype "passive"))
    )
    (net (code "124") (name "VCC3.3M") (class "Default")
      (node (ref "C11") (pin "1") (pintype "passive"))
      (node (ref "C12") (pin "1") (pintype "passive"))
      (node (ref "C13") (pin "1") (pintype "passive"))
      (node (ref "C14") (pin "1") (pintype "passive"))
      (node (ref "C15") (pin "1") (pintype "passive"))
      (node (ref "C16") (pin "1") (pintype "passive"))
      (node (ref "C17") (pin "1") (pintype "passive"))
      (node (ref "C18") (pin "1") (pintype "passive"))
      (node (ref "C19") (pin "1") (pintype "passive"))
      (node (ref "C20") (pin "1") (pintype "passive"))
      (node (ref "C21") (pin "1") (pintype "passive"))
      (node (ref "D1") (pin "1") (pintype "passive"))
      (node (ref "R7") (pin "2") (pintype "passive"))
      (node (ref "R8") (pin "2") (pintype "passive"))
      (node (ref "U1") (pin "108") (pinfunction "VDD_108") (pintype "passive"))
      (node (ref "U1") (pin "121") (pinfunction "VDD_121") (pintype "passive"))
      (node (ref "U1") (pin "131") (pinfunction "VDD_131") (pintype "passive"))
      (node (ref "U1") (pin "144") (pinfunction "VDD_144") (pintype "passive"))
      (node (ref "U1") (pin "17") (pinfunction "VDD_17") (pintype "passive"))
      (node (ref "U1") (pin "39") (pinfunction "VDD_39") (pintype "passive"))
      (node (ref "U1") (pin "52") (pinfunction "VDD_52") (pintype "passive"))
      (node (ref "U1") (pin "62") (pinfunction "VDD_62") (pintype "passive"))
      (node (ref "U1") (pin "72") (pinfunction "VDD_72") (pintype "passive"))
      (node (ref "U1") (pin "84") (pinfunction "VDD_84") (pintype "passive"))
      (node (ref "U1") (pin "95") (pinfunction "VDD_95") (pintype "passive"))
    )
    (net (code "125") (name "VCC5") (class "Default")
      (node (ref "P2") (pin "1") (pinfunction "1_1") (pintype "passive"))
      (node (ref "P2") (pin "3") (pinfunction "3_3") (pintype "passive"))
      (node (ref "P2") (pin "5") (pinfunction "5_5") (pintype "passive"))
    )
    (net (code "126") (name "VDDA") (class "Default")
      (node (ref "C8") (pin "2") (pintype "passive"))
      (node (ref "C9") (pin "2") (pintype "passive"))
      (node (ref "R3") (pin "1") (pintype "passive"))
      (node (ref "U1") (pin "32") (pinfunction "Vref+_32") (pintype "passive"))
      (node (ref "U1") (pin "33") (pinfunction "VDDA_33") (pintype "passive"))
    )
    (net (code "127") (name "unconnected-(U1-NC-Pad106)") (class "Default")
      (node (ref "U1") (pin "106") (pinfunction "NC_106") (pintype "passive"))
    )
  )
)
